# Amp_Kit_v5_3_-2016.net
KiCad netlist of a schematic drawn in EAGLE
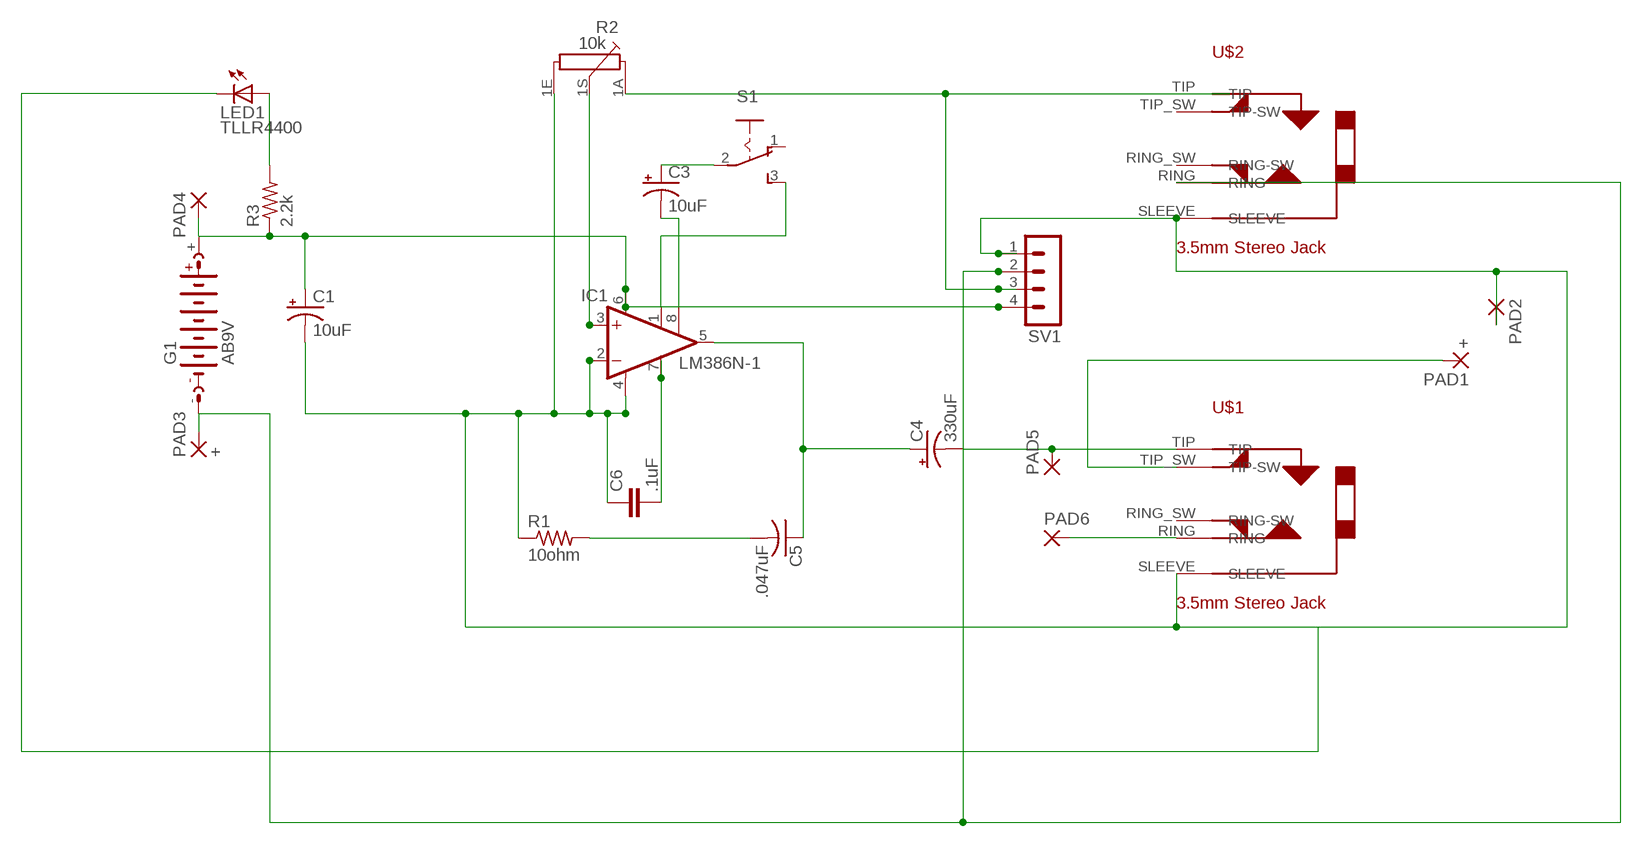
[diagram p0: schematic, sheet 1]

(export (version "E")
  (design (tool "Eeschema 10.0.6"))
  (components
    (comp (ref "C1")
      (value "10uF")
      (footprint "eagle-import:E2-5")
      (libsource (lib "eagle-import") (part "CPOL-USE2-5"))
    )
    (comp (ref "C3")
      (value "10uF")
      (footprint "eagle-import:E2-5")
      (libsource (lib "eagle-import") (part "CPOL-USE2-5"))
    )
    (comp (ref "C4")
      (value "330uF")
      (footprint "eagle-import:E3,5-8")
      (libsource (lib "eagle-import") (part "CPOL-USE3.5-8"))
    )
    (comp (ref "C5")
      (value ".047uF")
      (footprint "eagle-import:C050-025X075")
      (libsource (lib "eagle-import") (part "C-US050-025X075"))
    )
    (comp (ref "C6")
      (value ".1uF")
      (footprint "eagle-import:C050-035X075")
      (libsource (lib "eagle-import") (part "C-EU050-035X075"))
    )
    (comp (ref "G1")
      (value "AB9V")
      (footprint "eagle-import:AB9V")
      (libsource (lib "eagle-import") (part "AB9V"))
    )
    (comp (ref "IC1")
      (value "LM386N-1")
      (footprint "eagle-import:DIL08")
      (libsource (lib "eagle-import") (part "LM386?-N1"))
    )
    (comp (ref "LED1")
      (value "TLLR4400")
      (footprint "eagle-import:LED3MM")
      (fields (field (name "MF") "VISHAY SEMICONDUCTOR"))
      (libsource (lib "eagle-import") (part "TLLR4400"))
    )
    (comp (ref "PAD1")
      (value "+")
      (footprint "eagle-import:3,81_1,4")
      (libsource (lib "eagle-import") (part "3,81/1,4"))
    )
    (comp (ref "PAD2")
      (value "3,81/1,4")
      (footprint "eagle-import:3,81_1,4")
      (libsource (lib "eagle-import") (part "3,81/1,4"))
    )
    (comp (ref "PAD3")
      (value "+")
      (footprint "eagle-import:3,81_1,4")
      (libsource (lib "eagle-import") (part "3,81/1,4"))
    )
    (comp (ref "PAD4")
      (value "3,81/1,4")
      (footprint "eagle-import:3,81_1,4")
      (libsource (lib "eagle-import") (part "3,81/1,4"))
    )
    (comp (ref "PAD5")
      (value "SMD2")
      (footprint "eagle-import:SMD1,27-2,54")
      (libsource (lib "eagle-import") (part "SMD2"))
    )
    (comp (ref "PAD6")
      (value "SMD2")
      (footprint "eagle-import:SMD1,27-2,54")
      (libsource (lib "eagle-import") (part "SMD2"))
    )
    (comp (ref "R1")
      (value "10ohm")
      (footprint "eagle-import:0207_7")
      (libsource (lib "eagle-import") (part "R-US_0207/7"))
    )
    (comp (ref "R2")
      (value "10k")
      (footprint "eagle-import:PC16S")
      (libsource (lib "eagle-import") (part "PC16S"))
    )
    (comp (ref "R3")
      (value "2.2k")
      (footprint "eagle-import:0207_7")
      (libsource (lib "eagle-import") (part "R-US_0207/7"))
    )
    (comp (ref "S1")
      (value "255SB")
      (footprint "eagle-import:255SB")
      (libsource (lib "eagle-import") (part "255SB"))
    )
    (comp (ref "SV1")
      (value "MA04-1")
      (footprint "eagle-import:MA04-1")
      (libsource (lib "eagle-import") (part "MA04-1"))
    )
    (comp (ref "U$1")
      (value "PICAXE_STEREOJACKSOCKET")
      (footprint "eagle-import:PICAXE_STEREOJACKSOCKET")
      (libsource (lib "eagle-import") (part "PICAXE_STEREOJACKSOCKET"))
    )
    (comp (ref "U$2")
      (value "PICAXE_STEREOJACKSOCKET")
      (footprint "eagle-import:PICAXE_STEREOJACKSOCKET")
      (libsource (lib "eagle-import") (part "PICAXE_STEREOJACKSOCKET"))
    )
  )
  (nets
    (net (code "1") (name "Net-(C3-Pad-)") (class "Default")
      (node (ref "C3") (pin "-") (pinfunction "-_-") (pintype "passive"))
      (node (ref "IC1") (pin "8") (pinfunction "GAIN_8") (pintype "passive"))
    )
    (net (code "2") (name "Net-(C5-Pad2)") (class "Default")
      (node (ref "C5") (pin "2") (pinfunction "2_2") (pintype "passive"))
      (node (ref "R1") (pin "2") (pinfunction "2_2") (pintype "passive"))
    )
    (net (code "3") (name "Net-(IC1-+IN)") (class "Default")
      (node (ref "IC1") (pin "3") (pinfunction "+IN_3") (pintype "input"))
      (node (ref "R2") (pin "1S") (pinfunction "1S_1S") (pintype "passive"))
    )
    (net (code "4") (name "Net-(IC1--IN)") (class "Default")
      (node (ref "C1") (pin "-") (pinfunction "-_-") (pintype "passive"))
      (node (ref "C6") (pin "1") (pinfunction "1_1") (pintype "passive"))
      (node (ref "IC1") (pin "2") (pinfunction "-IN_2") (pintype "input"))
      (node (ref "IC1") (pin "4") (pinfunction "GND_4") (pintype "power_in"))
      (node (ref "LED1") (pin "K") (pinfunction "C_K") (pintype "passive"))
      (node (ref "PAD2") (pin "1") (pinfunction "P_1") (pintype "passive"))
      (node (ref "R1") (pin "1") (pinfunction "1_1") (pintype "passive"))
      (node (ref "R2") (pin "1E") (pinfunction "1E_1E") (pintype "passive"))
      (node (ref "SV1") (pin "1") (pinfunction "1_1") (pintype "passive"))
      (node (ref "U$1") (pin "SLEEVE") (pinfunction "SLEEVE_SLEEVE") (pintype "bidirectional"))
      (node (ref "U$2") (pin "SLEEVE") (pinfunction "SLEEVE_SLEEVE") (pintype "bidirectional"))
    )
    (net (code "5") (name "Net-(IC1-BYPASS)") (class "Default")
      (node (ref "C6") (pin "2") (pinfunction "2_2") (pintype "passive"))
      (node (ref "IC1") (pin "7") (pinfunction "BYPASS_7") (pintype "passive"))
    )
    (net (code "6") (name "Net-(IC1-OUT)") (class "Default")
      (node (ref "C4") (pin "+") (pinfunction "+_+") (pintype "passive"))
      (node (ref "C5") (pin "1") (pinfunction "1_1") (pintype "passive"))
      (node (ref "IC1") (pin "5") (pinfunction "OUT_5") (pintype "output"))
    )
    (net (code "7") (name "Net-(IC1-VS)") (class "Default")
      (node (ref "C1") (pin "+") (pinfunction "+_+") (pintype "passive"))
      (node (ref "G1") (pin "+") (pinfunction "+_+") (pintype "passive"))
      (node (ref "IC1") (pin "6") (pinfunction "VS_6") (pintype "power_in"))
      (node (ref "PAD4") (pin "1") (pinfunction "P_1") (pintype "passive"))
      (node (ref "R3") (pin "1") (pinfunction "1_1") (pintype "passive"))
      (node (ref "SV1") (pin "4") (pinfunction "4_4") (pintype "passive"))
    )
    (net (code "8") (name "Net-(LED1-PadA)") (class "Default")
      (node (ref "LED1") (pin "A") (pinfunction "A_A") (pintype "passive"))
      (node (ref "R3") (pin "2") (pinfunction "2_2") (pintype "passive"))
    )
    (net (code "9") (name "Net-(PAD1-P)") (class "Default")
      (node (ref "PAD1") (pin "1") (pinfunction "P_1") (pintype "passive"))
      (node (ref "U$1") (pin "TIP_SW") (pinfunction "TIP-SW_TIP_SW") (pintype "bidirectional"))
    )
    (net (code "10") (name "Net-(PAD3-P)") (class "Default")
      (node (ref "G1") (pin "-") (pinfunction "-_-") (pintype "passive"))
      (node (ref "PAD3") (pin "1") (pinfunction "P_1") (pintype "passive"))
      (node (ref "SV1") (pin "2") (pinfunction "2_2") (pintype "passive"))
      (node (ref "U$2") (pin "RING") (pinfunction "RING_RING") (pintype "bidirectional"))
    )
    (net (code "11") (name "Net-(PAD5-P)") (class "Default")
      (node (ref "C4") (pin "-") (pinfunction "-_-") (pintype "passive"))
      (node (ref "PAD5") (pin "1") (pinfunction "P_1") (pintype "passive"))
      (node (ref "U$1") (pin "TIP") (pinfunction "TIP_TIP") (pintype "bidirectional"))
    )
    (net (code "12") (name "Net-(PAD6-P)") (class "Default")
      (node (ref "PAD6") (pin "1") (pinfunction "P_1") (pintype "passive"))
      (node (ref "U$1") (pin "RING") (pinfunction "RING_RING") (pintype "bidirectional"))
    )
    (net (code "13") (name "Net-(R2-Pad1A)") (class "Default")
      (node (ref "R2") (pin "1A") (pinfunction "1A_1A") (pintype "passive"))
      (node (ref "SV1") (pin "3") (pinfunction "3_3") (pintype "passive"))
      (node (ref "U$2") (pin "TIP") (pinfunction "TIP_TIP") (pintype "bidirectional"))
    )
    (net (code "14") (name "Net-(S1-P)") (class "Default")
      (node (ref "C3") (pin "+") (pinfunction "+_+") (pintype "passive"))
      (node (ref "S1") (pin "2") (pinfunction "P_2") (pintype "passive"))
    )
    (net (code "15") (name "Net-(S1-S)") (class "Default")
      (node (ref "IC1") (pin "1") (pinfunction "GAIN_1") (pintype "passive"))
      (node (ref "S1") (pin "3") (pinfunction "S_3") (pintype "passive"))
    )
    (net (code "16") (name "unconnected-(S1-O-Pad1)") (class "Default")
      (node (ref "S1") (pin "1") (pinfunction "O_1") (pintype "passive"))
    )
    (net (code "17") (name "unconnected-(U$1-RING-SW-PadRING_SW)") (class "Default")
      (node (ref "U$1") (pin "RING_SW") (pinfunction "RING-SW_RING_SW") (pintype "bidirectional"))
    )
    (net (code "18") (name "unconnected-(U$2-RING-SW-PadRING_SW)") (class "Default")
      (node (ref "U$2") (pin "RING_SW") (pinfunction "RING-SW_RING_SW") (pintype "bidirectional"))
    )
    (net (code "19") (name "unconnected-(U$2-TIP-SW-PadTIP_SW)") (class "Default")
      (node (ref "U$2") (pin "TIP_SW") (pinfunction "TIP-SW_TIP_SW") (pintype "bidirectional"))
    )
  )
)
